# untitled.net
KiCad netlist of a schematic drawn in EAGLE
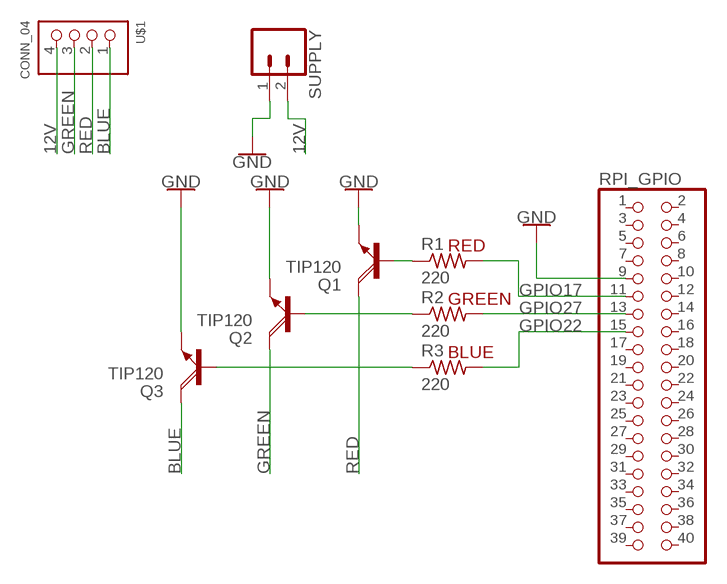
[diagram p0: schematic, sheet 1]

(export (version "E")
  (design (tool "Eeschema 10.0.6"))
  (components
    (comp (ref "Q1")
      (value "TIP120")
      (footprint "eagle-import:TO220AH")
      (libsource (lib "eagle-import") (part "TIP120"))
    )
    (comp (ref "Q2")
      (value "TIP120")
      (footprint "eagle-import:TO220AH")
      (libsource (lib "eagle-import") (part "TIP120"))
    )
    (comp (ref "Q3")
      (value "TIP120")
      (footprint "eagle-import:TO220AH")
      (libsource (lib "eagle-import") (part "TIP120"))
    )
    (comp (ref "R1")
      (value "220")
      (footprint "eagle-import:0207_10")
      (libsource (lib "eagle-import") (part "R-US_0207/10"))
    )
    (comp (ref "R2")
      (value "220")
      (footprint "eagle-import:0207_10")
      (libsource (lib "eagle-import") (part "R-US_0207/10"))
    )
    (comp (ref "R3")
      (value "220")
      (footprint "eagle-import:0207_10")
      (libsource (lib "eagle-import") (part "R-US_0207/10"))
    )
    (comp (ref "RPI_GPIO")
      (value "PINHD-2X20")
      (footprint "eagle-import:2X20")
      (libsource (lib "eagle-import") (part "PINHD-2X20"))
    )
    (comp (ref "SUPPLY")
      (value "CONN_025MM")
      (footprint "eagle-import:SCREWTERMINAL-5MM-2")
      (libsource (lib "eagle-import") (part "CONN_025MM"))
    )
    (comp (ref "U$1")
      (value "CONN_04")
      (footprint "eagle-import:SCREWTERMINAL-5MM-4")
      (libsource (lib "eagle-import") (part "CONN_04"))
    )
  )
  (nets
    (net (code "1") (name "/12V") (class "Default")
      (node (ref "SUPPLY") (pin "2") (pinfunction "2_2") (pintype "passive"))
      (node (ref "U$1") (pin "4") (pinfunction "4_4") (pintype "bidirectional"))
    )
    (net (code "2") (name "/BLUE") (class "Default")
      (node (ref "Q3") (pin "C") (pinfunction "C_C") (pintype "passive"))
      (node (ref "U$1") (pin "1") (pinfunction "1_1") (pintype "bidirectional"))
    )
    (net (code "3") (name "/GPIO17") (class "Default")
      (node (ref "R1") (pin "2") (pinfunction "2_2") (pintype "passive"))
      (node (ref "RPI_GPIO") (pin "11") (pinfunction "11_11") (pintype "passive"))
    )
    (net (code "4") (name "/GPIO22") (class "Default")
      (node (ref "R3") (pin "2") (pinfunction "2_2") (pintype "passive"))
      (node (ref "RPI_GPIO") (pin "15") (pinfunction "15_15") (pintype "passive"))
    )
    (net (code "5") (name "/GPIO27") (class "Default")
      (node (ref "R2") (pin "2") (pinfunction "2_2") (pintype "passive"))
      (node (ref "RPI_GPIO") (pin "13") (pinfunction "13_13") (pintype "passive"))
    )
    (net (code "6") (name "/GREEN") (class "Default")
      (node (ref "Q2") (pin "C") (pinfunction "C_C") (pintype "passive"))
      (node (ref "U$1") (pin "3") (pinfunction "3_3") (pintype "bidirectional"))
    )
    (net (code "7") (name "/RED") (class "Default")
      (node (ref "Q1") (pin "C") (pinfunction "C_C") (pintype "passive"))
      (node (ref "U$1") (pin "2") (pinfunction "2_2") (pintype "bidirectional"))
    )
    (net (code "8") (name "GND") (class "Default")
      (node (ref "Q1") (pin "E") (pinfunction "E_E") (pintype "passive"))
      (node (ref "Q2") (pin "E") (pinfunction "E_E") (pintype "passive"))
      (node (ref "Q3") (pin "E") (pinfunction "E_E") (pintype "passive"))
      (node (ref "RPI_GPIO") (pin "9") (pinfunction "9_9") (pintype "passive"))
      (node (ref "SUPPLY") (pin "1") (pinfunction "1_1") (pintype "passive"))
    )
    (net (code "9") (name "Net-(Q1-PadB)") (class "Default")
      (node (ref "Q1") (pin "B") (pinfunction "B_B") (pintype "passive"))
      (node (ref "R1") (pin "1") (pinfunction "1_1") (pintype "passive"))
    )
    (net (code "10") (name "Net-(Q2-PadB)") (class "Default")
      (node (ref "Q2") (pin "B") (pinfunction "B_B") (pintype "passive"))
      (node (ref "R2") (pin "1") (pinfunction "1_1") (pintype "passive"))
    )
    (net (code "11") (name "Net-(Q3-PadB)") (class "Default")
      (node (ref "Q3") (pin "B") (pinfunction "B_B") (pintype "passive"))
      (node (ref "R3") (pin "1") (pinfunction "1_1") (pintype "passive"))
    )
    (net (code "12") (name "unconnected-(RPI_GPIO-Pad1)") (class "Default")
      (node (ref "RPI_GPIO") (pin "1") (pinfunction "1_1") (pintype "passive"))
    )
    (net (code "13") (name "unconnected-(RPI_GPIO-Pad2)") (class "Default")
      (node (ref "RPI_GPIO") (pin "2") (pinfunction "2_2") (pintype "passive"))
    )
    (net (code "14") (name "unconnected-(RPI_GPIO-Pad3)") (class "Default")
      (node (ref "RPI_GPIO") (pin "3") (pinfunction "3_3") (pintype "passive"))
    )
    (net (code "15") (name "unconnected-(RPI_GPIO-Pad4)") (class "Default")
      (node (ref "RPI_GPIO") (pin "4") (pinfunction "4_4") (pintype "passive"))
    )
    (net (code "16") (name "unconnected-(RPI_GPIO-Pad5)") (class "Default")
      (node (ref "RPI_GPIO") (pin "5") (pinfunction "5_5") (pintype "passive"))
    )
    (net (code "17") (name "unconnected-(RPI_GPIO-Pad6)") (class "Default")
      (node (ref "RPI_GPIO") (pin "6") (pinfunction "6_6") (pintype "passive"))
    )
    (net (code "18") (name "unconnected-(RPI_GPIO-Pad7)") (class "Default")
      (node (ref "RPI_GPIO") (pin "7") (pinfunction "7_7") (pintype "passive"))
    )
    (net (code "19") (name "unconnected-(RPI_GPIO-Pad8)") (class "Default")
      (node (ref "RPI_GPIO") (pin "8") (pinfunction "8_8") (pintype "passive"))
    )
    (net (code "20") (name "unconnected-(RPI_GPIO-Pad10)") (class "Default")
      (node (ref "RPI_GPIO") (pin "10") (pinfunction "10_10") (pintype "passive"))
    )
    (net (code "21") (name "unconnected-(RPI_GPIO-Pad12)") (class "Default")
      (node (ref "RPI_GPIO") (pin "12") (pinfunction "12_12") (pintype "passive"))
    )
    (net (code "22") (name "unconnected-(RPI_GPIO-Pad14)") (class "Default")
      (node (ref "RPI_GPIO") (pin "14") (pinfunction "14_14") (pintype "passive"))
    )
    (net (code "23") (name "unconnected-(RPI_GPIO-Pad16)") (class "Default")
      (node (ref "RPI_GPIO") (pin "16") (pinfunction "16_16") (pintype "passive"))
    )
    (net (code "24") (name "unconnected-(RPI_GPIO-Pad17)") (class "Default")
      (node (ref "RPI_GPIO") (pin "17") (pinfunction "17_17") (pintype "passive"))
    )
    (net (code "25") (name "unconnected-(RPI_GPIO-Pad18)") (class "Default")
      (node (ref "RPI_GPIO") (pin "18") (pinfunction "18_18") (pintype "passive"))
    )
    (net (code "26") (name "unconnected-(RPI_GPIO-Pad19)") (class "Default")
      (node (ref "RPI_GPIO") (pin "19") (pinfunction "19_19") (pintype "passive"))
    )
    (net (code "27") (name "unconnected-(RPI_GPIO-Pad20)") (class "Default")
      (node (ref "RPI_GPIO") (pin "20") (pinfunction "20_20") (pintype "passive"))
    )
    (net (code "28") (name "unconnected-(RPI_GPIO-Pad21)") (class "Default")
      (node (ref "RPI_GPIO") (pin "21") (pinfunction "21_21") (pintype "passive"))
    )
    (net (code "29") (name "unconnected-(RPI_GPIO-Pad22)") (class "Default")
      (node (ref "RPI_GPIO") (pin "22") (pinfunction "22_22") (pintype "passive"))
    )
    (net (code "30") (name "unconnected-(RPI_GPIO-Pad23)") (class "Default")
      (node (ref "RPI_GPIO") (pin "23") (pinfunction "23_23") (pintype "passive"))
    )
    (net (code "31") (name "unconnected-(RPI_GPIO-Pad24)") (class "Default")
      (node (ref "RPI_GPIO") (pin "24") (pinfunction "24_24") (pintype "passive"))
    )
    (net (code "32") (name "unconnected-(RPI_GPIO-Pad25)") (class "Default")
      (node (ref "RPI_GPIO") (pin "25") (pinfunction "25_25") (pintype "passive"))
    )
    (net (code "33") (name "unconnected-(RPI_GPIO-Pad26)") (class "Default")
      (node (ref "RPI_GPIO") (pin "26") (pinfunction "26_26") (pintype "passive"))
    )
    (net (code "34") (name "unconnected-(RPI_GPIO-Pad27)") (class "Default")
      (node (ref "RPI_GPIO") (pin "27") (pinfunction "27_27") (pintype "passive"))
    )
    (net (code "35") (name "unconnected-(RPI_GPIO-Pad28)") (class "Default")
      (node (ref "RPI_GPIO") (pin "28") (pinfunction "28_28") (pintype "passive"))
    )
    (net (code "36") (name "unconnected-(RPI_GPIO-Pad29)") (class "Default")
      (node (ref "RPI_GPIO") (pin "29") (pinfunction "29_29") (pintype "passive"))
    )
    (net (code "37") (name "unconnected-(RPI_GPIO-Pad30)") (class "Default")
      (node (ref "RPI_GPIO") (pin "30") (pinfunction "30_30") (pintype "passive"))
    )
    (net (code "38") (name "unconnected-(RPI_GPIO-Pad31)") (class "Default")
      (node (ref "RPI_GPIO") (pin "31") (pinfunction "31_31") (pintype "passive"))
    )
    (net (code "39") (name "unconnected-(RPI_GPIO-Pad32)") (class "Default")
      (node (ref "RPI_GPIO") (pin "32") (pinfunction "32_32") (pintype "passive"))
    )
    (net (code "40") (name "unconnected-(RPI_GPIO-Pad33)") (class "Default")
      (node (ref "RPI_GPIO") (pin "33") (pinfunction "33_33") (pintype "passive"))
    )
    (net (code "41") (name "unconnected-(RPI_GPIO-Pad34)") (class "Default")
      (node (ref "RPI_GPIO") (pin "34") (pinfunction "34_34") (pintype "passive"))
    )
    (net (code "42") (name "unconnected-(RPI_GPIO-Pad35)") (class "Default")
      (node (ref "RPI_GPIO") (pin "35") (pinfunction "35_35") (pintype "passive"))
    )
    (net (code "43") (name "unconnected-(RPI_GPIO-Pad36)") (class "Default")
      (node (ref "RPI_GPIO") (pin "36") (pinfunction "36_36") (pintype "passive"))
    )
    (net (code "44") (name "unconnected-(RPI_GPIO-Pad37)") (class "Default")
      (node (ref "RPI_GPIO") (pin "37") (pinfunction "37_37") (pintype "passive"))
    )
    (net (code "45") (name "unconnected-(RPI_GPIO-Pad38)") (class "Default")
      (node (ref "RPI_GPIO") (pin "38") (pinfunction "38_38") (pintype "passive"))
    )
    (net (code "46") (name "unconnected-(RPI_GPIO-Pad39)") (class "Default")
      (node (ref "RPI_GPIO") (pin "39") (pinfunction "39_39") (pintype "passive"))
    )
    (net (code "47") (name "unconnected-(RPI_GPIO-Pad40)") (class "Default")
      (node (ref "RPI_GPIO") (pin "40") (pinfunction "40_40") (pintype "passive"))
    )
  )
)
